# RaspberryPI4.net
KiCad netlist of a schematic drawn in Altium Designer
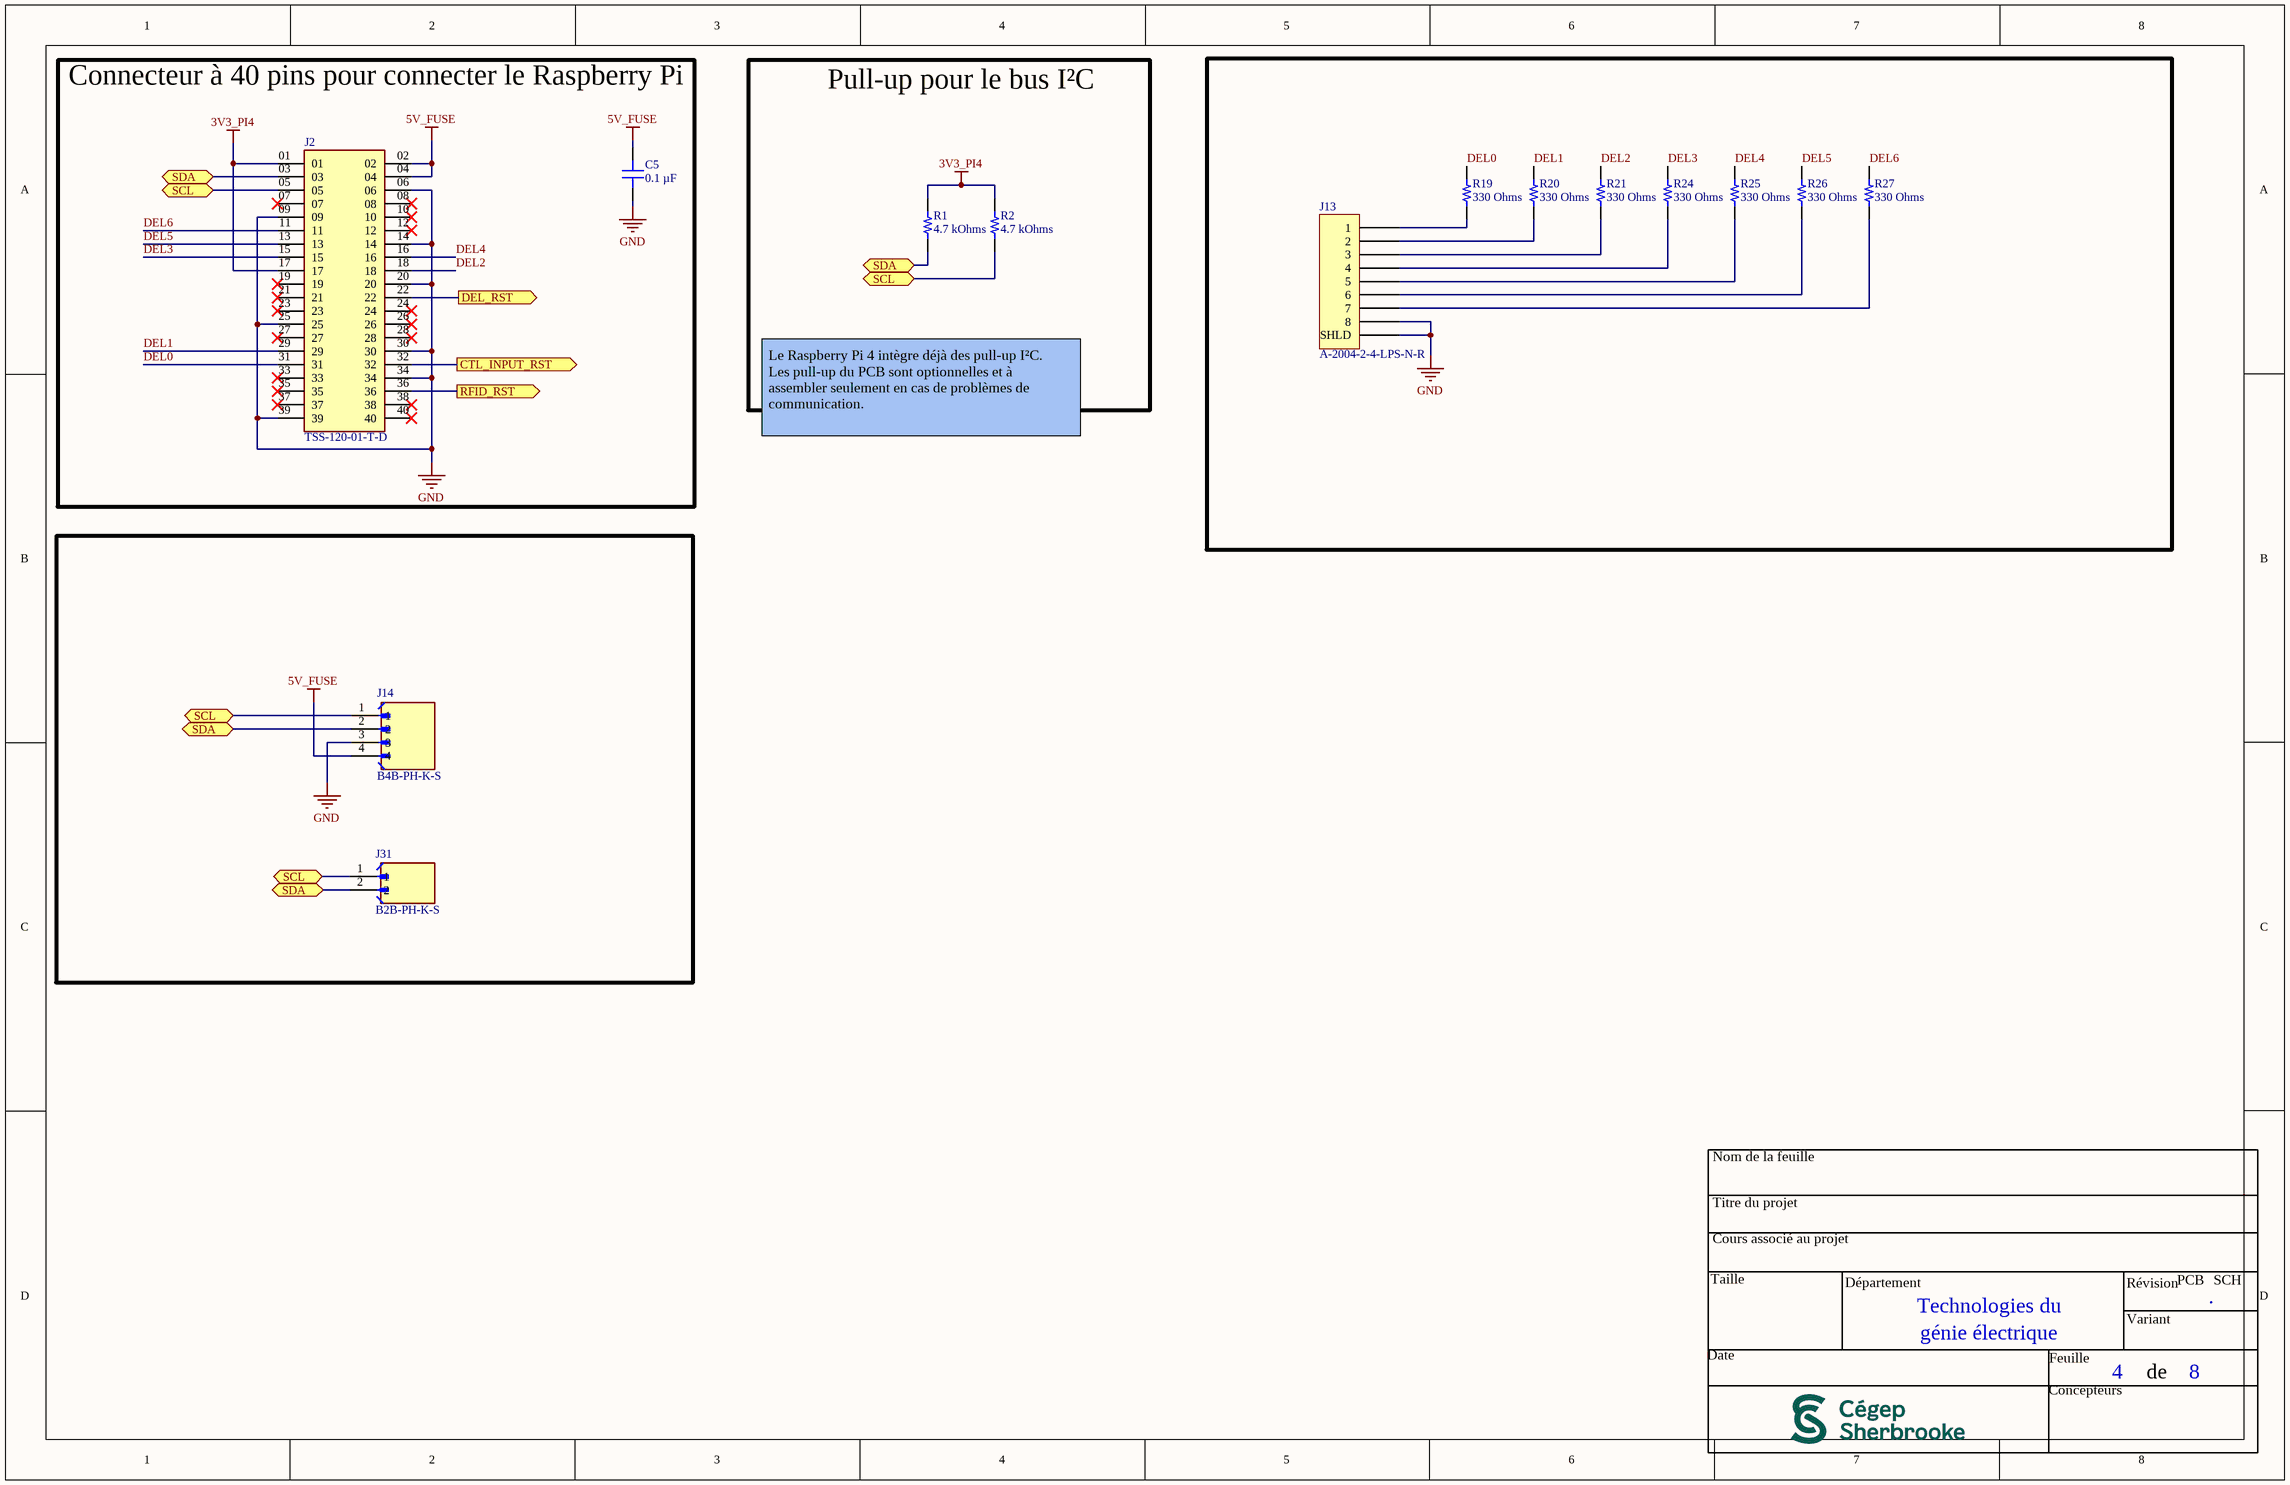
[diagram p0: RaspberryPI4.SchDoc]

(export (version "E")
  (design (tool "Eeschema 10.0.6"))
  (components
    (comp (ref "C5")
      (value "0.1 µF")
      (footprint "CAP 0805_2012")
      (description "CAP CER 0.1UF 25V X7R 0805")
      (fields
        (field (name "PART NUMBER") "0805J0250104KXT")
        (field (name "CAPACITANCE") "0.1 µF")
        (field (name "MANUFACTURER") "Knowles Syfer")
      )
      (libsource (lib "Celestial Altium Library - altium_library") (part "Capacitor"))
    )
    (comp (ref "J2")
      (value "TSS-120-01-T-D")
      (footprint "SAMTEC_TSS-120-01-T-D")
      (description "Connector Header Through Hole 40 position 0.100 (2.54mm)")
      (fields (field (name "MF") "Samtec"))
      (libsource (lib "TSS-120-01-T-D") (part "TSS-120-01-T-D"))
    )
    (comp (ref "J13")
      (value "A-2004-2-4-LPS-N-R")
      (footprint "ASSMANN A-2004-2-4-LPS-N-R")
      (description "CONN MOD JACK 8P8C R/A SHIELDED")
      (fields (field (name "MANUFACTURER") "Assmann WSW Components"))
      (libsource (lib "Celestial Altium Library - altium_library") (part "Modular Jack with Shield"))
    )
    (comp (ref "J14")
      (value "B4B-PH-K-S")
      (footprint "JST_B4B-PH-K-S")
      (fields (field (name "MF") "{'manufacturer': u'JST Sales America Inc.'}"))
      (libsource (lib "B4B-PH-K-S") (part "B4B-PH-K-S"))
    )
    (comp (ref "J31")
      (value "B2B-PH-K-S")
      (footprint "JST_B2B-PH-K-S")
      (description "Connector Header Through Hole 2 position 0.079 (2.00mm)")
      (fields (field (name "MF") "JST Sales America Inc."))
      (libsource (lib "B2B-PH-K-S") (part "B2B-PH-K-S"))
    )
    (comp (ref "R1")
      (value "4.7 kOhms")
      (footprint "RES 0603_1608")
      (description "RES SMD 4.7K OHM 5% 1/4W 0603")
      (fields (field (name "PART NUMBER") "ESR03EZPJ472") (field (name "MANUFACTURER") "Rohm Semiconductor"))
      (libsource (lib "Celestial Altium Library - altium_library") (part "Resistor"))
    )
    (comp (ref "R2")
      (value "4.7 kOhms")
      (footprint "RES 0603_1608")
      (description "RES SMD 4.7K OHM 5% 1/4W 0603")
      (fields (field (name "PART NUMBER") "ESR03EZPJ472") (field (name "MANUFACTURER") "Rohm Semiconductor"))
      (libsource (lib "Celestial Altium Library - altium_library") (part "Resistor"))
    )
    (comp (ref "R19")
      (value "330 Ohms")
      (footprint "RES 0805_2012")
      (description "RES SMD 330 OHM 0.1% 1/4W 0805")
      (fields
        (field (name "PART NUMBER") "ERJ-PB6B3300V")
        (field (name "MANUFACTURER") "Panasonic Electronic Components")
      )
      (libsource (lib "Celestial Altium Library - altium_library") (part "Resistor"))
    )
    (comp (ref "R20")
      (value "330 Ohms")
      (footprint "RES 0805_2012")
      (description "RES SMD 330 OHM 0.1% 1/4W 0805")
      (fields
        (field (name "PART NUMBER") "ERJ-PB6B3300V")
        (field (name "MANUFACTURER") "Panasonic Electronic Components")
      )
      (libsource (lib "Celestial Altium Library - altium_library") (part "Resistor"))
    )
    (comp (ref "R21")
      (value "330 Ohms")
      (footprint "RES 0805_2012")
      (description "RES SMD 330 OHM 0.1% 1/4W 0805")
      (fields
        (field (name "PART NUMBER") "ERJ-PB6B3300V")
        (field (name "MANUFACTURER") "Panasonic Electronic Components")
      )
      (libsource (lib "Celestial Altium Library - altium_library") (part "Resistor"))
    )
    (comp (ref "R24")
      (value "330 Ohms")
      (footprint "RES 0805_2012")
      (description "RES SMD 330 OHM 0.1% 1/4W 0805")
      (fields
        (field (name "PART NUMBER") "ERJ-PB6B3300V")
        (field (name "MANUFACTURER") "Panasonic Electronic Components")
      )
      (libsource (lib "Celestial Altium Library - altium_library") (part "Resistor"))
    )
    (comp (ref "R25")
      (value "330 Ohms")
      (footprint "RES 0805_2012")
      (description "RES SMD 330 OHM 0.1% 1/4W 0805")
      (fields
        (field (name "PART NUMBER") "ERJ-PB6B3300V")
        (field (name "MANUFACTURER") "Panasonic Electronic Components")
      )
      (libsource (lib "Celestial Altium Library - altium_library") (part "Resistor"))
    )
    (comp (ref "R26")
      (value "330 Ohms")
      (footprint "RES 0805_2012")
      (description "RES SMD 330 OHM 0.1% 1/4W 0805")
      (fields
        (field (name "PART NUMBER") "ERJ-PB6B3300V")
        (field (name "MANUFACTURER") "Panasonic Electronic Components")
      )
      (libsource (lib "Celestial Altium Library - altium_library") (part "Resistor"))
    )
    (comp (ref "R27")
      (value "330 Ohms")
      (footprint "RES 0805_2012")
      (description "RES SMD 330 OHM 0.1% 1/4W 0805")
      (fields
        (field (name "PART NUMBER") "ERJ-PB6B3300V")
        (field (name "MANUFACTURER") "Panasonic Electronic Components")
      )
      (libsource (lib "Celestial Altium Library - altium_library") (part "Resistor"))
    )
  )
  (nets
    (net (code "1") (name "/CTL_INPUT_RST") (class "Default")
      (node (ref "J2") (pin "32") (pinfunction "32_32") (pintype "passive"))
    )
    (net (code "2") (name "/DEL0") (class "Default")
      (node (ref "J2") (pin "31") (pinfunction "31_31") (pintype "passive"))
      (node (ref "R19") (pin "2") (pinfunction "2_2") (pintype "passive"))
    )
    (net (code "3") (name "/DEL1") (class "Default")
      (node (ref "J2") (pin "29") (pinfunction "29_29") (pintype "passive"))
      (node (ref "R20") (pin "2") (pinfunction "2_2") (pintype "passive"))
    )
    (net (code "4") (name "/DEL2") (class "Default")
      (node (ref "J2") (pin "18") (pinfunction "18_18") (pintype "passive"))
      (node (ref "R21") (pin "2") (pinfunction "2_2") (pintype "passive"))
    )
    (net (code "5") (name "/DEL3") (class "Default")
      (node (ref "J2") (pin "15") (pinfunction "15_15") (pintype "passive"))
      (node (ref "R24") (pin "2") (pinfunction "2_2") (pintype "passive"))
    )
    (net (code "6") (name "/DEL4") (class "Default")
      (node (ref "J2") (pin "16") (pinfunction "16_16") (pintype "passive"))
      (node (ref "R25") (pin "2") (pinfunction "2_2") (pintype "passive"))
    )
    (net (code "7") (name "/DEL5") (class "Default")
      (node (ref "J2") (pin "13") (pinfunction "13_13") (pintype "passive"))
      (node (ref "R26") (pin "2") (pinfunction "2_2") (pintype "passive"))
    )
    (net (code "8") (name "/DEL6") (class "Default")
      (node (ref "J2") (pin "11") (pinfunction "11_11") (pintype "passive"))
      (node (ref "R27") (pin "2") (pinfunction "2_2") (pintype "passive"))
    )
    (net (code "9") (name "/DEL_RST") (class "Default")
      (node (ref "J2") (pin "22") (pinfunction "22_22") (pintype "passive"))
    )
    (net (code "10") (name "/RFID_RST") (class "Default")
      (node (ref "J2") (pin "36") (pinfunction "36_36") (pintype "passive"))
    )
    (net (code "11") (name "/SCL") (class "Default")
      (node (ref "J14") (pin "1") (pinfunction "1_1") (pintype "passive"))
      (node (ref "J2") (pin "05") (pinfunction "05_05") (pintype "passive"))
      (node (ref "J31") (pin "1") (pinfunction "1_1") (pintype "passive"))
      (node (ref "R2") (pin "1") (pinfunction "1_1") (pintype "passive"))
    )
    (net (code "12") (name "/SDA") (class "Default")
      (node (ref "J14") (pin "2") (pinfunction "2_2") (pintype "passive"))
      (node (ref "J2") (pin "03") (pinfunction "03_03") (pintype "passive"))
      (node (ref "J31") (pin "2") (pinfunction "2_2") (pintype "passive"))
      (node (ref "R1") (pin "1") (pinfunction "1_1") (pintype "passive"))
    )
    (net (code "13") (name "3V3_PI4") (class "Default")
      (node (ref "J2") (pin "01") (pinfunction "01_01") (pintype "passive"))
      (node (ref "J2") (pin "17") (pinfunction "17_17") (pintype "passive"))
      (node (ref "R1") (pin "2") (pinfunction "2_2") (pintype "passive"))
      (node (ref "R2") (pin "2") (pinfunction "2_2") (pintype "passive"))
    )
    (net (code "14") (name "5V_FUSE") (class "Default")
      (node (ref "C5") (pin "2") (pinfunction "2_2") (pintype "passive"))
      (node (ref "J14") (pin "4") (pinfunction "4_4") (pintype "passive"))
      (node (ref "J2") (pin "02") (pinfunction "02_02") (pintype "passive"))
      (node (ref "J2") (pin "04") (pinfunction "04_04") (pintype "passive"))
    )
    (net (code "15") (name "GND") (class "Default")
      (node (ref "C5") (pin "1") (pinfunction "1_1") (pintype "passive"))
      (node (ref "J13") (pin "8") (pinfunction "8_8") (pintype "passive"))
      (node (ref "J13") (pin "S") (pinfunction "SHLD_S") (pintype "passive"))
      (node (ref "J14") (pin "3") (pinfunction "3_3") (pintype "passive"))
      (node (ref "J2") (pin "06") (pinfunction "06_06") (pintype "passive"))
      (node (ref "J2") (pin "09") (pinfunction "09_09") (pintype "passive"))
      (node (ref "J2") (pin "14") (pinfunction "14_14") (pintype "passive"))
      (node (ref "J2") (pin "20") (pinfunction "20_20") (pintype "passive"))
      (node (ref "J2") (pin "25") (pinfunction "25_25") (pintype "passive"))
      (node (ref "J2") (pin "30") (pinfunction "30_30") (pintype "passive"))
      (node (ref "J2") (pin "34") (pinfunction "34_34") (pintype "passive"))
      (node (ref "J2") (pin "39") (pinfunction "39_39") (pintype "passive"))
    )
    (net (code "16") (name "Net-(J13-Pad1)") (class "Default")
      (node (ref "J13") (pin "1") (pinfunction "1_1") (pintype "passive"))
      (node (ref "R19") (pin "1") (pinfunction "1_1") (pintype "passive"))
    )
    (net (code "17") (name "Net-(J13-Pad2)") (class "Default")
      (node (ref "J13") (pin "2") (pinfunction "2_2") (pintype "passive"))
      (node (ref "R20") (pin "1") (pinfunction "1_1") (pintype "passive"))
    )
    (net (code "18") (name "Net-(J13-Pad3)") (class "Default")
      (node (ref "J13") (pin "3") (pinfunction "3_3") (pintype "passive"))
      (node (ref "R21") (pin "1") (pinfunction "1_1") (pintype "passive"))
    )
    (net (code "19") (name "Net-(J13-Pad4)") (class "Default")
      (node (ref "J13") (pin "4") (pinfunction "4_4") (pintype "passive"))
      (node (ref "R24") (pin "1") (pinfunction "1_1") (pintype "passive"))
    )
    (net (code "20") (name "Net-(J13-Pad5)") (class "Default")
      (node (ref "J13") (pin "5") (pinfunction "5_5") (pintype "passive"))
      (node (ref "R25") (pin "1") (pinfunction "1_1") (pintype "passive"))
    )
    (net (code "21") (name "Net-(J13-Pad6)") (class "Default")
      (node (ref "J13") (pin "6") (pinfunction "6_6") (pintype "passive"))
      (node (ref "R26") (pin "1") (pinfunction "1_1") (pintype "passive"))
    )
    (net (code "22") (name "Net-(J13-Pad7)") (class "Default")
      (node (ref "J13") (pin "7") (pinfunction "7_7") (pintype "passive"))
      (node (ref "R27") (pin "1") (pinfunction "1_1") (pintype "passive"))
    )
    (net (code "23") (name "unconnected-(J2-Pad07)") (class "Default")
      (node (ref "J2") (pin "07") (pinfunction "07_07") (pintype "passive+no_connect"))
    )
    (net (code "24") (name "unconnected-(J2-Pad08)") (class "Default")
      (node (ref "J2") (pin "08") (pinfunction "08_08") (pintype "passive+no_connect"))
    )
    (net (code "25") (name "unconnected-(J2-Pad10)") (class "Default")
      (node (ref "J2") (pin "10") (pinfunction "10_10") (pintype "passive+no_connect"))
    )
    (net (code "26") (name "unconnected-(J2-Pad12)") (class "Default")
      (node (ref "J2") (pin "12") (pinfunction "12_12") (pintype "passive+no_connect"))
    )
    (net (code "27") (name "unconnected-(J2-Pad19)") (class "Default")
      (node (ref "J2") (pin "19") (pinfunction "19_19") (pintype "passive+no_connect"))
    )
    (net (code "28") (name "unconnected-(J2-Pad21)") (class "Default")
      (node (ref "J2") (pin "21") (pinfunction "21_21") (pintype "passive+no_connect"))
    )
    (net (code "29") (name "unconnected-(J2-Pad23)") (class "Default")
      (node (ref "J2") (pin "23") (pinfunction "23_23") (pintype "passive+no_connect"))
    )
    (net (code "30") (name "unconnected-(J2-Pad24)") (class "Default")
      (node (ref "J2") (pin "24") (pinfunction "24_24") (pintype "passive+no_connect"))
    )
    (net (code "31") (name "unconnected-(J2-Pad26)") (class "Default")
      (node (ref "J2") (pin "26") (pinfunction "26_26") (pintype "passive+no_connect"))
    )
    (net (code "32") (name "unconnected-(J2-Pad27)") (class "Default")
      (node (ref "J2") (pin "27") (pinfunction "27_27") (pintype "passive+no_connect"))
    )
    (net (code "33") (name "unconnected-(J2-Pad28)") (class "Default")
      (node (ref "J2") (pin "28") (pinfunction "28_28") (pintype "passive+no_connect"))
    )
    (net (code "34") (name "unconnected-(J2-Pad33)") (class "Default")
      (node (ref "J2") (pin "33") (pinfunction "33_33") (pintype "passive+no_connect"))
    )
    (net (code "35") (name "unconnected-(J2-Pad35)") (class "Default")
      (node (ref "J2") (pin "35") (pinfunction "35_35") (pintype "passive+no_connect"))
    )
    (net (code "36") (name "unconnected-(J2-Pad37)") (class "Default")
      (node (ref "J2") (pin "37") (pinfunction "37_37") (pintype "passive+no_connect"))
    )
    (net (code "37") (name "unconnected-(J2-Pad38)") (class "Default")
      (node (ref "J2") (pin "38") (pinfunction "38_38") (pintype "passive+no_connect"))
    )
    (net (code "38") (name "unconnected-(J2-Pad40)") (class "Default")
      (node (ref "J2") (pin "40") (pinfunction "40_40") (pintype "passive+no_connect"))
    )
  )
)
